# undershield-pro-mini-rev2.net
KiCad netlist of a schematic drawn in EAGLE
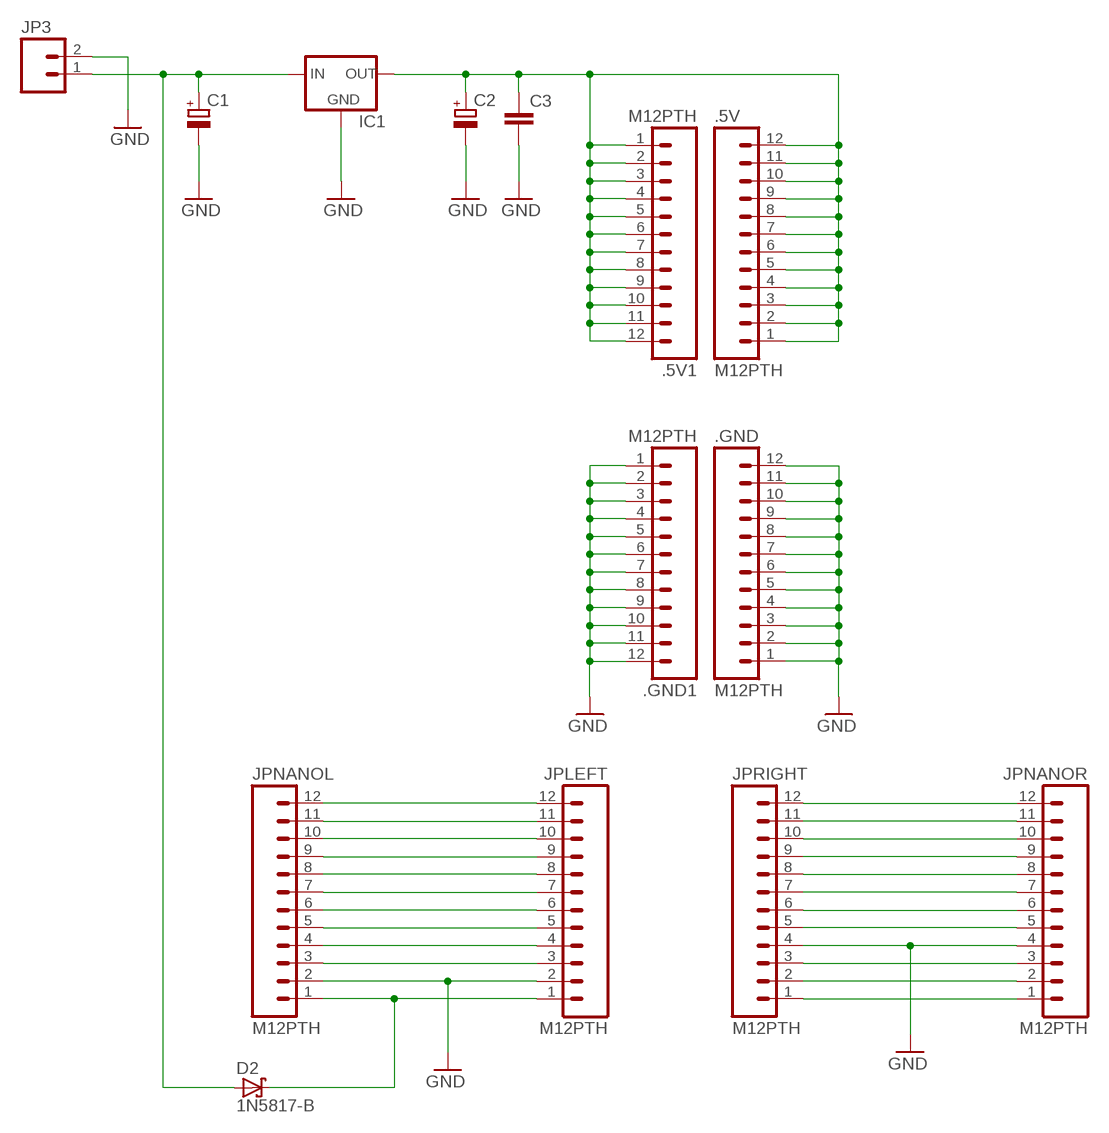
[diagram p0: schematic, sheet 1]

(export (version "E")
  (design (tool "Eeschema 10.0.6"))
  (components
    (comp (ref ".5V")
      (value "M12PTH")
      (footprint "eagle-import:1X12")
      (libsource (lib "eagle-import") (part "M12PTH"))
    )
    (comp (ref ".5V1")
      (value "M12PTH")
      (footprint "eagle-import:1X12")
      (libsource (lib "eagle-import") (part "M12PTH"))
    )
    (comp (ref ".GND")
      (value "M12PTH")
      (footprint "eagle-import:1X12")
      (libsource (lib "eagle-import") (part "M12PTH"))
    )
    (comp (ref ".GND1")
      (value "M12PTH")
      (footprint "eagle-import:1X12")
      (libsource (lib "eagle-import") (part "M12PTH"))
    )
    (comp (ref "C1")
      (value "CPOL-EUE2.5-6")
      (footprint "eagle-import:E2,5-6")
      (libsource (lib "eagle-import") (part "CPOL-EUE2.5-6"))
    )
    (comp (ref "C2")
      (value "CPOL-EUE2.5-5")
      (footprint "eagle-import:E2,5-5")
      (libsource (lib "eagle-import") (part "CPOL-EUE2.5-5"))
    )
    (comp (ref "C3")
      (value "C-EU025-025X050")
      (footprint "eagle-import:C025-025X050")
      (libsource (lib "eagle-import") (part "C-EU025-025X050"))
    )
    (comp (ref "D2")
      (value "1N5817-B")
      (footprint "eagle-import:DO41-7.6")
      (libsource (lib "eagle-import") (part "1N5817-B"))
    )
    (comp (ref "IC1")
      (value "V_REG_78XX-TO-220")
      (footprint "eagle-import:TO-220-ALT")
      (libsource (lib "eagle-import") (part "V_REG_78XX-TO-220"))
    )
    (comp (ref "JP3")
      (value "M023.5MM")
      (footprint "eagle-import:SCREWTERMINAL-3.5MM-2")
      (libsource (lib "eagle-import") (part "M023.5MM"))
    )
    (comp (ref "JPLEFT")
      (value "M12PTH")
      (footprint "eagle-import:1X12")
      (libsource (lib "eagle-import") (part "M12PTH"))
    )
    (comp (ref "JPNANOL")
      (value "M12PTH")
      (footprint "eagle-import:1X12")
      (libsource (lib "eagle-import") (part "M12PTH"))
    )
    (comp (ref "JPNANOR")
      (value "M12PTH")
      (footprint "eagle-import:1X12")
      (libsource (lib "eagle-import") (part "M12PTH"))
    )
    (comp (ref "JPRIGHT")
      (value "M12PTH")
      (footprint "eagle-import:1X12")
      (libsource (lib "eagle-import") (part "M12PTH"))
    )
  )
  (nets
    (net (code "1") (name "GND") (class "Default")
      (node (ref ".GND") (pin "1") (pinfunction "1_1") (pintype "passive"))
      (node (ref ".GND") (pin "10") (pinfunction "10_10") (pintype "passive"))
      (node (ref ".GND") (pin "11") (pinfunction "11_11") (pintype "passive"))
      (node (ref ".GND") (pin "12") (pinfunction "12_12") (pintype "passive"))
      (node (ref ".GND") (pin "2") (pinfunction "2_2") (pintype "passive"))
      (node (ref ".GND") (pin "3") (pinfunction "3_3") (pintype "passive"))
      (node (ref ".GND") (pin "4") (pinfunction "4_4") (pintype "passive"))
      (node (ref ".GND") (pin "5") (pinfunction "5_5") (pintype "passive"))
      (node (ref ".GND") (pin "6") (pinfunction "6_6") (pintype "passive"))
      (node (ref ".GND") (pin "7") (pinfunction "7_7") (pintype "passive"))
      (node (ref ".GND") (pin "8") (pinfunction "8_8") (pintype "passive"))
      (node (ref ".GND") (pin "9") (pinfunction "9_9") (pintype "passive"))
      (node (ref ".GND1") (pin "1") (pinfunction "1_1") (pintype "passive"))
      (node (ref ".GND1") (pin "10") (pinfunction "10_10") (pintype "passive"))
      (node (ref ".GND1") (pin "11") (pinfunction "11_11") (pintype "passive"))
      (node (ref ".GND1") (pin "12") (pinfunction "12_12") (pintype "passive"))
      (node (ref ".GND1") (pin "2") (pinfunction "2_2") (pintype "passive"))
      (node (ref ".GND1") (pin "3") (pinfunction "3_3") (pintype "passive"))
      (node (ref ".GND1") (pin "4") (pinfunction "4_4") (pintype "passive"))
      (node (ref ".GND1") (pin "5") (pinfunction "5_5") (pintype "passive"))
      (node (ref ".GND1") (pin "6") (pinfunction "6_6") (pintype "passive"))
      (node (ref ".GND1") (pin "7") (pinfunction "7_7") (pintype "passive"))
      (node (ref ".GND1") (pin "8") (pinfunction "8_8") (pintype "passive"))
      (node (ref ".GND1") (pin "9") (pinfunction "9_9") (pintype "passive"))
      (node (ref "C1") (pin "-") (pinfunction "-_-") (pintype "passive"))
      (node (ref "C2") (pin "-") (pinfunction "-_-") (pintype "passive"))
      (node (ref "C3") (pin "2") (pinfunction "2_2") (pintype "passive"))
      (node (ref "IC1") (pin "GND") (pinfunction "GND_GND") (pintype "input"))
      (node (ref "JP3") (pin "2") (pinfunction "2_2") (pintype "passive"))
      (node (ref "JPLEFT") (pin "2") (pinfunction "2_2") (pintype "passive"))
      (node (ref "JPNANOL") (pin "2") (pinfunction "2_2") (pintype "passive"))
      (node (ref "JPNANOR") (pin "4") (pinfunction "4_4") (pintype "passive"))
      (node (ref "JPRIGHT") (pin "4") (pinfunction "4_4") (pintype "passive"))
    )
    (net (code "2") (name "Net-(.5V-Pad1)") (class "Default")
      (node (ref ".5V") (pin "1") (pinfunction "1_1") (pintype "passive"))
      (node (ref ".5V") (pin "10") (pinfunction "10_10") (pintype "passive"))
      (node (ref ".5V") (pin "11") (pinfunction "11_11") (pintype "passive"))
      (node (ref ".5V") (pin "12") (pinfunction "12_12") (pintype "passive"))
      (node (ref ".5V") (pin "2") (pinfunction "2_2") (pintype "passive"))
      (node (ref ".5V") (pin "3") (pinfunction "3_3") (pintype "passive"))
      (node (ref ".5V") (pin "4") (pinfunction "4_4") (pintype "passive"))
      (node (ref ".5V") (pin "5") (pinfunction "5_5") (pintype "passive"))
      (node (ref ".5V") (pin "6") (pinfunction "6_6") (pintype "passive"))
      (node (ref ".5V") (pin "7") (pinfunction "7_7") (pintype "passive"))
      (node (ref ".5V") (pin "8") (pinfunction "8_8") (pintype "passive"))
      (node (ref ".5V") (pin "9") (pinfunction "9_9") (pintype "passive"))
      (node (ref ".5V1") (pin "1") (pinfunction "1_1") (pintype "passive"))
      (node (ref ".5V1") (pin "10") (pinfunction "10_10") (pintype "passive"))
      (node (ref ".5V1") (pin "11") (pinfunction "11_11") (pintype "passive"))
      (node (ref ".5V1") (pin "12") (pinfunction "12_12") (pintype "passive"))
      (node (ref ".5V1") (pin "2") (pinfunction "2_2") (pintype "passive"))
      (node (ref ".5V1") (pin "3") (pinfunction "3_3") (pintype "passive"))
      (node (ref ".5V1") (pin "4") (pinfunction "4_4") (pintype "passive"))
      (node (ref ".5V1") (pin "5") (pinfunction "5_5") (pintype "passive"))
      (node (ref ".5V1") (pin "6") (pinfunction "6_6") (pintype "passive"))
      (node (ref ".5V1") (pin "7") (pinfunction "7_7") (pintype "passive"))
      (node (ref ".5V1") (pin "8") (pinfunction "8_8") (pintype "passive"))
      (node (ref ".5V1") (pin "9") (pinfunction "9_9") (pintype "passive"))
      (node (ref "C2") (pin "+") (pinfunction "+_+") (pintype "passive"))
      (node (ref "C3") (pin "1") (pinfunction "1_1") (pintype "passive"))
      (node (ref "IC1") (pin "OUT") (pinfunction "OUT_OUT") (pintype "output"))
    )
    (net (code "3") (name "Net-(C1-Pad+)") (class "Default")
      (node (ref "C1") (pin "+") (pinfunction "+_+") (pintype "passive"))
      (node (ref "D2") (pin "A") (pinfunction "A_A") (pintype "passive"))
      (node (ref "IC1") (pin "IN") (pinfunction "IN_IN") (pintype "input"))
      (node (ref "JP3") (pin "1") (pinfunction "1_1") (pintype "passive"))
    )
    (net (code "4") (name "Net-(D2-PadC)") (class "Default")
      (node (ref "D2") (pin "C") (pinfunction "C_C") (pintype "passive"))
      (node (ref "JPLEFT") (pin "1") (pinfunction "1_1") (pintype "passive"))
      (node (ref "JPNANOL") (pin "1") (pinfunction "1_1") (pintype "passive"))
    )
    (net (code "5") (name "Net-(JPLEFT-Pad3)") (class "Default")
      (node (ref "JPLEFT") (pin "3") (pinfunction "3_3") (pintype "passive"))
      (node (ref "JPNANOL") (pin "3") (pinfunction "3_3") (pintype "passive"))
    )
    (net (code "6") (name "Net-(JPLEFT-Pad4)") (class "Default")
      (node (ref "JPLEFT") (pin "4") (pinfunction "4_4") (pintype "passive"))
      (node (ref "JPNANOL") (pin "4") (pinfunction "4_4") (pintype "passive"))
    )
    (net (code "7") (name "Net-(JPLEFT-Pad5)") (class "Default")
      (node (ref "JPLEFT") (pin "5") (pinfunction "5_5") (pintype "passive"))
      (node (ref "JPNANOL") (pin "5") (pinfunction "5_5") (pintype "passive"))
    )
    (net (code "8") (name "Net-(JPLEFT-Pad6)") (class "Default")
      (node (ref "JPLEFT") (pin "6") (pinfunction "6_6") (pintype "passive"))
      (node (ref "JPNANOL") (pin "6") (pinfunction "6_6") (pintype "passive"))
    )
    (net (code "9") (name "Net-(JPLEFT-Pad7)") (class "Default")
      (node (ref "JPLEFT") (pin "7") (pinfunction "7_7") (pintype "passive"))
      (node (ref "JPNANOL") (pin "7") (pinfunction "7_7") (pintype "passive"))
    )
    (net (code "10") (name "Net-(JPLEFT-Pad8)") (class "Default")
      (node (ref "JPLEFT") (pin "8") (pinfunction "8_8") (pintype "passive"))
      (node (ref "JPNANOL") (pin "8") (pinfunction "8_8") (pintype "passive"))
    )
    (net (code "11") (name "Net-(JPLEFT-Pad9)") (class "Default")
      (node (ref "JPLEFT") (pin "9") (pinfunction "9_9") (pintype "passive"))
      (node (ref "JPNANOL") (pin "9") (pinfunction "9_9") (pintype "passive"))
    )
    (net (code "12") (name "Net-(JPLEFT-Pad10)") (class "Default")
      (node (ref "JPLEFT") (pin "10") (pinfunction "10_10") (pintype "passive"))
      (node (ref "JPNANOL") (pin "10") (pinfunction "10_10") (pintype "passive"))
    )
    (net (code "13") (name "Net-(JPLEFT-Pad11)") (class "Default")
      (node (ref "JPLEFT") (pin "11") (pinfunction "11_11") (pintype "passive"))
      (node (ref "JPNANOL") (pin "11") (pinfunction "11_11") (pintype "passive"))
    )
    (net (code "14") (name "Net-(JPLEFT-Pad12)") (class "Default")
      (node (ref "JPLEFT") (pin "12") (pinfunction "12_12") (pintype "passive"))
      (node (ref "JPNANOL") (pin "12") (pinfunction "12_12") (pintype "passive"))
    )
    (net (code "15") (name "Net-(JPNANOR-Pad1)") (class "Default")
      (node (ref "JPNANOR") (pin "1") (pinfunction "1_1") (pintype "passive"))
      (node (ref "JPRIGHT") (pin "1") (pinfunction "1_1") (pintype "passive"))
    )
    (net (code "16") (name "Net-(JPNANOR-Pad2)") (class "Default")
      (node (ref "JPNANOR") (pin "2") (pinfunction "2_2") (pintype "passive"))
      (node (ref "JPRIGHT") (pin "2") (pinfunction "2_2") (pintype "passive"))
    )
    (net (code "17") (name "Net-(JPNANOR-Pad3)") (class "Default")
      (node (ref "JPNANOR") (pin "3") (pinfunction "3_3") (pintype "passive"))
      (node (ref "JPRIGHT") (pin "3") (pinfunction "3_3") (pintype "passive"))
    )
    (net (code "18") (name "Net-(JPNANOR-Pad5)") (class "Default")
      (node (ref "JPNANOR") (pin "5") (pinfunction "5_5") (pintype "passive"))
      (node (ref "JPRIGHT") (pin "5") (pinfunction "5_5") (pintype "passive"))
    )
    (net (code "19") (name "Net-(JPNANOR-Pad6)") (class "Default")
      (node (ref "JPNANOR") (pin "6") (pinfunction "6_6") (pintype "passive"))
      (node (ref "JPRIGHT") (pin "6") (pinfunction "6_6") (pintype "passive"))
    )
    (net (code "20") (name "Net-(JPNANOR-Pad7)") (class "Default")
      (node (ref "JPNANOR") (pin "7") (pinfunction "7_7") (pintype "passive"))
      (node (ref "JPRIGHT") (pin "7") (pinfunction "7_7") (pintype "passive"))
    )
    (net (code "21") (name "Net-(JPNANOR-Pad8)") (class "Default")
      (node (ref "JPNANOR") (pin "8") (pinfunction "8_8") (pintype "passive"))
      (node (ref "JPRIGHT") (pin "8") (pinfunction "8_8") (pintype "passive"))
    )
    (net (code "22") (name "Net-(JPNANOR-Pad9)") (class "Default")
      (node (ref "JPNANOR") (pin "9") (pinfunction "9_9") (pintype "passive"))
      (node (ref "JPRIGHT") (pin "9") (pinfunction "9_9") (pintype "passive"))
    )
    (net (code "23") (name "Net-(JPNANOR-Pad10)") (class "Default")
      (node (ref "JPNANOR") (pin "10") (pinfunction "10_10") (pintype "passive"))
      (node (ref "JPRIGHT") (pin "10") (pinfunction "10_10") (pintype "passive"))
    )
    (net (code "24") (name "Net-(JPNANOR-Pad11)") (class "Default")
      (node (ref "JPNANOR") (pin "11") (pinfunction "11_11") (pintype "passive"))
      (node (ref "JPRIGHT") (pin "11") (pinfunction "11_11") (pintype "passive"))
    )
    (net (code "25") (name "Net-(JPNANOR-Pad12)") (class "Default")
      (node (ref "JPNANOR") (pin "12") (pinfunction "12_12") (pintype "passive"))
      (node (ref "JPRIGHT") (pin "12") (pinfunction "12_12") (pintype "passive"))
    )
  )
)
